# MCPS_Power_030524.net
KiCad netlist of a schematic drawn in Altium Designer
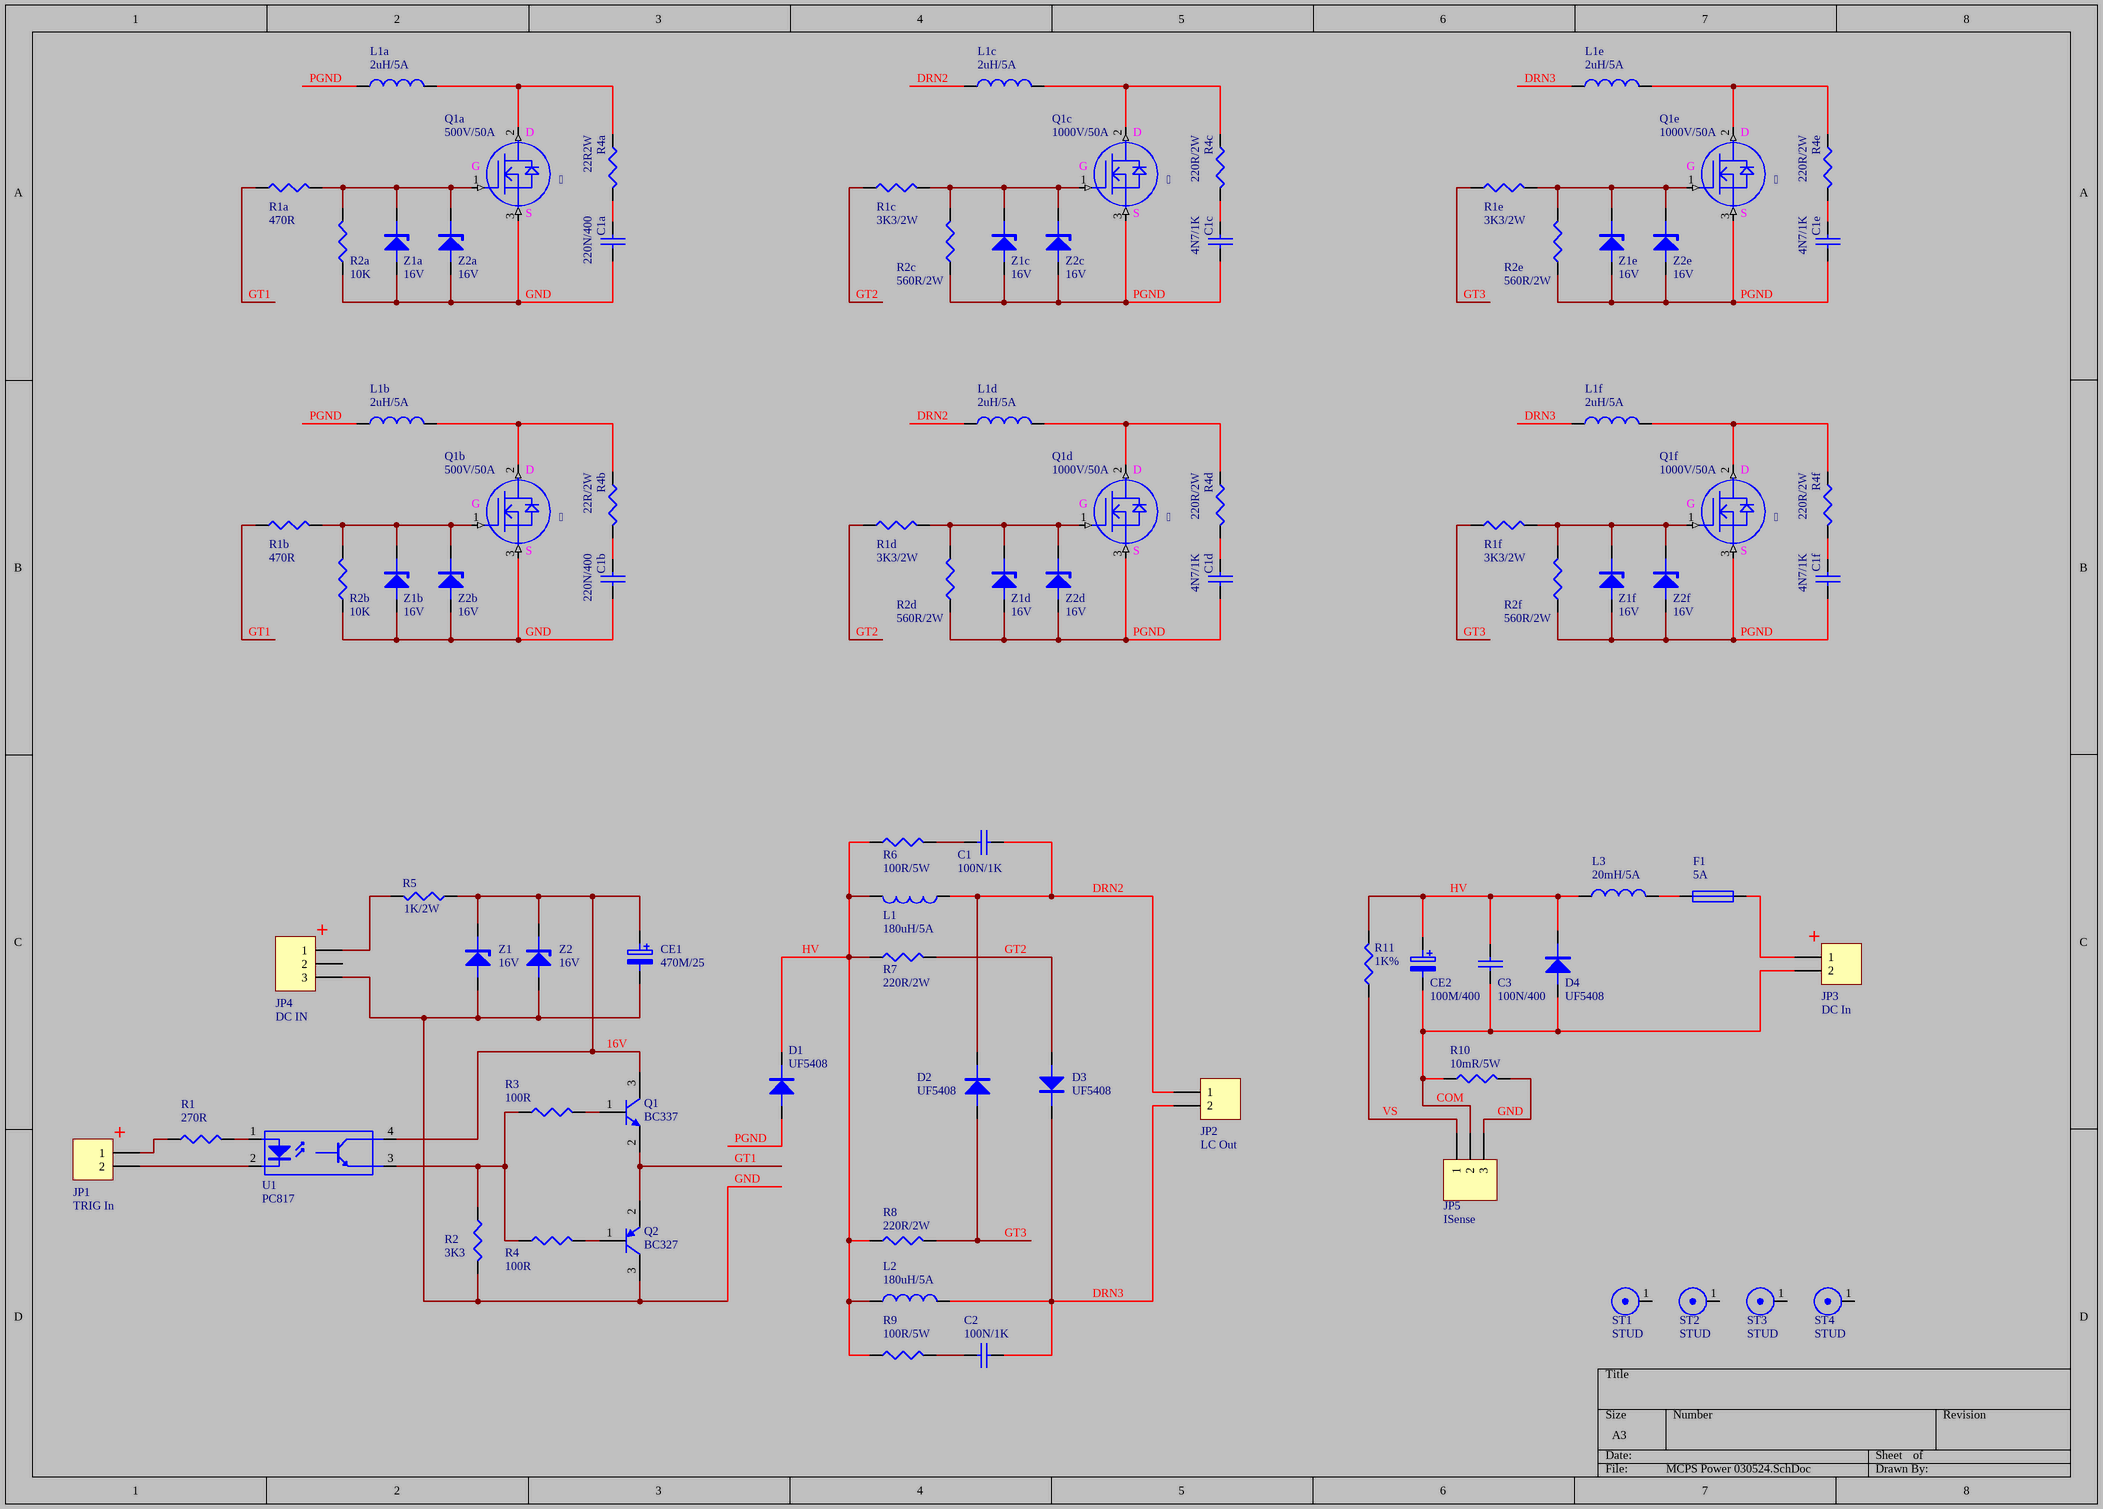
[diagram p0: MCPS Power 030524.SchDoc]

(export (version "E")
  (design (tool "Eeschema 10.0.6"))
  (components
    (comp (ref "C1") (value "100N/1K") (footprint "C100N") (libsource (lib "*") (part "C")))
    (comp (ref "C1a") (value "220N/400") (footprint "C4P") (libsource (lib "*") (part "C")))
    (comp (ref "C1b") (value "220N/400") (footprint "C4P") (libsource (lib "*") (part "C")))
    (comp (ref "C1c") (value "4N7/1K") (footprint "C4P") (libsource (lib "*") (part "C")))
    (comp (ref "C1d") (value "4N7/1K") (footprint "C4P") (libsource (lib "*") (part "C")))
    (comp (ref "C1e") (value "4N7/1K") (footprint "C4P") (libsource (lib "*") (part "C")))
    (comp (ref "C1f") (value "4N7/1K") (footprint "C4P") (libsource (lib "*") (part "C")))
    (comp (ref "C2") (value "100N/1K") (footprint "C100N") (libsource (lib "*") (part "C")))
    (comp (ref "C3") (value "100N/400") (footprint "C4P") (libsource (lib "*") (part "C")))
    (comp (ref "CE1") (value "470M/25") (footprint "cap2p12") (libsource (lib "*") (part "E")))
    (comp (ref "CE2") (value "100M/400") (footprint "CAP3P5") (libsource (lib "*") (part "E")))
    (comp (ref "D1") (value "UF5408") (footprint "D54") (libsource (lib "MyAltiumLib9702") (part "D")))
    (comp (ref "D2") (value "UF5408") (footprint "D54") (libsource (lib "MyAltiumLib9702") (part "D")))
    (comp (ref "D3") (value "UF5408") (footprint "D54") (libsource (lib "MyAltiumLib9702") (part "D")))
    (comp (ref "D4") (value "UF5408") (footprint "D54") (libsource (lib "MyAltiumLib9702") (part "D")))
    (comp (ref "F1") (value "5A") (footprint "FL") (libsource (lib "1402 Schlib 2020") (part "FUSE1")))
    (comp (ref "JP1")
      (value "TRIG In")
      (footprint "DSIP2")
      (description "Header, 2-Pin")
      (fields (field (name "PUBLISHER") "Altium Limited"))
      (libsource (lib "Miscellaneous Connectors") (part "Header 2"))
    )
    (comp (ref "JP2")
      (value "LC Out")
      (footprint "DG55X2")
      (description "Header, 2-Pin")
      (fields (field (name "PUBLISHER") "Altium Limited"))
      (libsource (lib "") (part "Header 2_1"))
    )
    (comp (ref "JP3")
      (value "DC In")
      (footprint "DG55X2")
      (description "Header, 2-Pin")
      (fields (field (name "PUBLISHER") "Altium Limited"))
      (libsource (lib "") (part "Header 2_1"))
    )
    (comp (ref "JP4")
      (value "DC IN")
      (footprint "DSIP3")
      (description "Header, 3-Pin")
      (fields (field (name "PUBLISHER") "Altium Limited"))
      (libsource (lib "") (part "Header 3_1"))
    )
    (comp (ref "JP5")
      (value "ISense")
      (footprint "DSIP3")
      (description "Header, 3-Pin")
      (fields (field (name "PUBLISHER") "Altium Limited"))
      (libsource (lib "1403 Schlib 2020") (part "Header 3"))
    )
    (comp (ref "L1") (value "180uH/5A") (footprint "L20MHGREEN") (libsource (lib "") (part "INDUCTOR_1")))
    (comp (ref "L1a")
      (value "2uH/5A")
      (footprint "LS_GREEN")
      (libsource (lib "MyAltiumLib9702") (part "INDUCTOR"))
    )
    (comp (ref "L1b")
      (value "2uH/5A")
      (footprint "LS_GREEN")
      (libsource (lib "MyAltiumLib9702") (part "INDUCTOR"))
    )
    (comp (ref "L1c")
      (value "2uH/5A")
      (footprint "LS_GREEN")
      (libsource (lib "MyAltiumLib9702") (part "INDUCTOR"))
    )
    (comp (ref "L1d")
      (value "2uH/5A")
      (footprint "LS_GREEN")
      (libsource (lib "MyAltiumLib9702") (part "INDUCTOR"))
    )
    (comp (ref "L1e")
      (value "2uH/5A")
      (footprint "LS_GREEN")
      (libsource (lib "MyAltiumLib9702") (part "INDUCTOR"))
    )
    (comp (ref "L1f")
      (value "2uH/5A")
      (footprint "LS_GREEN")
      (libsource (lib "MyAltiumLib9702") (part "INDUCTOR"))
    )
    (comp (ref "L2")
      (value "180uH/5A")
      (footprint "L20MHGREEN")
      (libsource (lib "MyAltiumLib9702") (part "INDUCTOR"))
    )
    (comp (ref "L3")
      (value "20mH/5A")
      (footprint "L20MHGREEN")
      (libsource (lib "MyAltiumLib9702") (part "INDUCTOR"))
    )
    (comp (ref "Q1")
      (value "BC337")
      (footprint "CBE-BC546")
      (libsource (lib "1402 Schlib 2020") (part "BC546"))
    )
    (comp (ref "Q1a")
      (value "")
      (footprint "3EDG-STR")
      (libsource (lib "1402 Schlib 2020") (part "MOSFET N"))
    )
    (comp (ref "Q1b")
      (value "")
      (footprint "3EDG-STR")
      (libsource (lib "1402 Schlib 2020") (part "MOSFET N"))
    )
    (comp (ref "Q1c")
      (value "")
      (footprint "3EDG-STR")
      (libsource (lib "1402 Schlib 2020") (part "MOSFET N"))
    )
    (comp (ref "Q1d")
      (value "")
      (footprint "3EDG-STR")
      (libsource (lib "1402 Schlib 2020") (part "MOSFET N"))
    )
    (comp (ref "Q1e")
      (value "")
      (footprint "3EDG-STR")
      (libsource (lib "1402 Schlib 2020") (part "MOSFET N"))
    )
    (comp (ref "Q1f")
      (value "")
      (footprint "3EDG-STR")
      (libsource (lib "1402 Schlib 2020") (part "MOSFET N"))
    )
    (comp (ref "Q2")
      (value "BC327")
      (footprint "CBE-BC546")
      (description "PNP")
      (fields (field (name "PUBLISHER") "Altium Limited"))
      (libsource (lib "1402 Schlib 2020") (part "M6"))
    )
    (comp (ref "R1") (value "270R") (footprint "W1/4") (libsource (lib "*") (part "R")))
    (comp (ref "R1a") (value "470R") (footprint "R5P") (libsource (lib "*") (part "R")))
    (comp (ref "R1b") (value "470R") (footprint "R5P") (libsource (lib "*") (part "R")))
    (comp (ref "R1c") (value "3K3/2W") (footprint "R2W") (libsource (lib "*") (part "R")))
    (comp (ref "R1d") (value "3K3/2W") (footprint "R2W") (libsource (lib "*") (part "R")))
    (comp (ref "R1e") (value "3K3/2W") (footprint "R2W") (libsource (lib "*") (part "R")))
    (comp (ref "R1f") (value "3K3/2W") (footprint "R2W") (libsource (lib "*") (part "R")))
    (comp (ref "R2") (value "3K3") (footprint "W1/4") (libsource (lib "*") (part "R")))
    (comp (ref "R2a") (value "10K") (footprint "R5P") (libsource (lib "*") (part "R")))
    (comp (ref "R2b") (value "10K") (footprint "R5P") (libsource (lib "*") (part "R")))
    (comp (ref "R2c") (value "560R/2W") (footprint "R2W") (libsource (lib "*") (part "R")))
    (comp (ref "R2d") (value "560R/2W") (footprint "R2W") (libsource (lib "*") (part "R")))
    (comp (ref "R2e") (value "560R/2W") (footprint "R2W") (libsource (lib "*") (part "R")))
    (comp (ref "R2f") (value "560R/2W") (footprint "R2W") (libsource (lib "*") (part "R")))
    (comp (ref "R3") (value "100R") (footprint "W1/4") (libsource (lib "*") (part "R")))
    (comp (ref "R4") (value "100R") (footprint "W1/4") (libsource (lib "*") (part "R")))
    (comp (ref "R4a") (value "22R2W") (footprint "R2W") (libsource (lib "*") (part "R")))
    (comp (ref "R4b") (value "22R/2W") (footprint "R2W") (libsource (lib "*") (part "R")))
    (comp (ref "R4c") (value "220R/2W") (footprint "R2W") (libsource (lib "*") (part "R")))
    (comp (ref "R4d") (value "220R/2W") (footprint "R2W") (libsource (lib "*") (part "R")))
    (comp (ref "R4e") (value "220R/2W") (footprint "R2W") (libsource (lib "*") (part "R")))
    (comp (ref "R4f") (value "220R/2W") (footprint "R2W") (libsource (lib "*") (part "R")))
    (comp (ref "R5") (value "1K/2W") (footprint "R2W") (libsource (lib "*") (part "R")))
    (comp (ref "R6") (value "100R/5W") (footprint "R5W") (libsource (lib "*") (part "R")))
    (comp (ref "R7") (value "220R/2W") (footprint "R2W") (libsource (lib "*") (part "R")))
    (comp (ref "R8") (value "220R/2W") (footprint "R2W") (libsource (lib "*") (part "R")))
    (comp (ref "R9") (value "100R/5W") (footprint "R5W") (libsource (lib "*") (part "R")))
    (comp (ref "R10") (value "10mR/5W") (footprint "R5W") (libsource (lib "*") (part "R")))
    (comp (ref "R11") (value "1K%") (footprint "R5P") (libsource (lib "*") (part "R")))
    (comp (ref "ST1") (value "STUD") (footprint "CORNER") (libsource (lib "1402 Schlib 2020") (part "STUD")))
    (comp (ref "ST2") (value "STUD") (footprint "CORNER") (libsource (lib "1402 Schlib 2020") (part "STUD")))
    (comp (ref "ST3") (value "STUD") (footprint "CORNER") (libsource (lib "1402 Schlib 2020") (part "STUD")))
    (comp (ref "ST4") (value "STUD") (footprint "CORNER") (libsource (lib "1402 Schlib 2020") (part "STUD")))
    (comp (ref "U1")
      (value "PC817")
      (footprint "DIP4")
      (libsource (lib "1402 Schlib 2020") (part "OPTODIP4"))
    )
    (comp (ref "Z1") (value "16V") (footprint "D5P") (libsource (lib "MyAltiumLib9702") (part "DZ")))
    (comp (ref "Z1a") (value "16V") (footprint "D5P") (libsource (lib "MyAltiumLib9702") (part "DZ")))
    (comp (ref "Z1b") (value "16V") (footprint "D5P") (libsource (lib "MyAltiumLib9702") (part "DZ")))
    (comp (ref "Z1c") (value "16V") (footprint "D5P") (libsource (lib "MyAltiumLib9702") (part "DZ")))
    (comp (ref "Z1d") (value "16V") (footprint "D5P") (libsource (lib "MyAltiumLib9702") (part "DZ")))
    (comp (ref "Z1e") (value "16V") (footprint "D5P") (libsource (lib "MyAltiumLib9702") (part "DZ")))
    (comp (ref "Z1f") (value "16V") (footprint "D5P") (libsource (lib "MyAltiumLib9702") (part "DZ")))
    (comp (ref "Z2") (value "16V") (footprint "D5P") (libsource (lib "MyAltiumLib9702") (part "DZ")))
    (comp (ref "Z2a") (value "16V") (footprint "D5P") (libsource (lib "MyAltiumLib9702") (part "DZ")))
    (comp (ref "Z2b") (value "16V") (footprint "D5P") (libsource (lib "MyAltiumLib9702") (part "DZ")))
    (comp (ref "Z2c") (value "16V") (footprint "D5P") (libsource (lib "MyAltiumLib9702") (part "DZ")))
    (comp (ref "Z2d") (value "16V") (footprint "D5P") (libsource (lib "MyAltiumLib9702") (part "DZ")))
    (comp (ref "Z2e") (value "16V") (footprint "D5P") (libsource (lib "MyAltiumLib9702") (part "DZ")))
    (comp (ref "Z2f") (value "16V") (footprint "D5P") (libsource (lib "MyAltiumLib9702") (part "DZ")))
  )
  (nets
    (net (code "1") (name "/16V") (class "Default")
      (node (ref "CE1") (pin "1") (pintype "passive"))
      (node (ref "Q1") (pin "3") (pinfunction "C_3") (pintype "passive"))
      (node (ref "R5") (pin "1") (pintype "passive"))
      (node (ref "U1") (pin "4") (pinfunction "C_4") (pintype "passive"))
      (node (ref "Z1") (pin "2") (pinfunction "K_2") (pintype "passive"))
      (node (ref "Z2") (pin "2") (pinfunction "K_2") (pintype "passive"))
    )
    (net (code "2") (name "/COM") (class "Default")
      (node (ref "C3") (pin "2") (pintype "passive"))
      (node (ref "CE2") (pin "2") (pintype "passive"))
      (node (ref "D4") (pin "1") (pinfunction "A_1") (pintype "passive"))
      (node (ref "JP3") (pin "2") (pinfunction "2_2") (pintype "passive"))
      (node (ref "JP5") (pin "2") (pinfunction "2_2") (pintype "passive"))
      (node (ref "R10") (pin "1") (pintype "passive"))
    )
    (net (code "3") (name "/DRN2") (class "Default")
      (node (ref "C1") (pin "2") (pintype "passive"))
      (node (ref "D2") (pin "2") (pinfunction "K_2") (pintype "passive"))
      (node (ref "JP2") (pin "1") (pinfunction "1_1") (pintype "passive"))
      (node (ref "L1") (pin "2") (pinfunction "2_2") (pintype "passive"))
      (node (ref "L1c") (pin "1") (pinfunction "1_1") (pintype "passive"))
      (node (ref "L1d") (pin "1") (pinfunction "1_1") (pintype "passive"))
    )
    (net (code "4") (name "/DRN3") (class "Default")
      (node (ref "C2") (pin "2") (pintype "passive"))
      (node (ref "D3") (pin "2") (pinfunction "K_2") (pintype "passive"))
      (node (ref "JP2") (pin "2") (pinfunction "2_2") (pintype "passive"))
      (node (ref "L1e") (pin "1") (pinfunction "1_1") (pintype "passive"))
      (node (ref "L1f") (pin "1") (pinfunction "1_1") (pintype "passive"))
      (node (ref "L2") (pin "2") (pinfunction "2_2") (pintype "passive"))
    )
    (net (code "5") (name "/GND") (class "Default")
      (node (ref "C1a") (pin "2") (pintype "passive"))
      (node (ref "C1b") (pin "2") (pintype "passive"))
      (node (ref "CE1") (pin "2") (pintype "passive"))
      (node (ref "JP4") (pin "3") (pinfunction "3_3") (pintype "passive"))
      (node (ref "JP5") (pin "3") (pinfunction "3_3") (pintype "passive"))
      (node (ref "Q1a") (pin "3") (pinfunction "S_3") (pintype "input"))
      (node (ref "Q1b") (pin "3") (pinfunction "S_3") (pintype "input"))
      (node (ref "Q2") (pin "3") (pinfunction "C_3") (pintype "passive"))
      (node (ref "R10") (pin "2") (pintype "passive"))
      (node (ref "R2") (pin "2") (pintype "passive"))
      (node (ref "R2a") (pin "1") (pintype "passive"))
      (node (ref "R2b") (pin "1") (pintype "passive"))
      (node (ref "Z1") (pin "1") (pinfunction "A_1") (pintype "passive"))
      (node (ref "Z1a") (pin "1") (pinfunction "A_1") (pintype "passive"))
      (node (ref "Z1b") (pin "1") (pinfunction "A_1") (pintype "passive"))
      (node (ref "Z2") (pin "1") (pinfunction "A_1") (pintype "passive"))
      (node (ref "Z2a") (pin "1") (pinfunction "A_1") (pintype "passive"))
      (node (ref "Z2b") (pin "1") (pinfunction "A_1") (pintype "passive"))
    )
    (net (code "6") (name "/GT1") (class "Default")
      (node (ref "Q1") (pin "2") (pinfunction "E_2") (pintype "passive"))
      (node (ref "Q2") (pin "2") (pinfunction "B_2") (pintype "passive"))
      (node (ref "R1a") (pin "1") (pintype "passive"))
      (node (ref "R1b") (pin "1") (pintype "passive"))
    )
    (net (code "7") (name "/GT2") (class "Default")
      (node (ref "D3") (pin "1") (pinfunction "A_1") (pintype "passive"))
      (node (ref "R1c") (pin "1") (pintype "passive"))
      (node (ref "R1d") (pin "1") (pintype "passive"))
      (node (ref "R7") (pin "2") (pintype "passive"))
    )
    (net (code "8") (name "/GT3") (class "Default")
      (node (ref "D2") (pin "1") (pinfunction "A_1") (pintype "passive"))
      (node (ref "R1e") (pin "1") (pintype "passive"))
      (node (ref "R1f") (pin "1") (pintype "passive"))
      (node (ref "R8") (pin "2") (pintype "passive"))
    )
    (net (code "9") (name "/HV") (class "Default")
      (node (ref "C3") (pin "1") (pintype "passive"))
      (node (ref "CE2") (pin "1") (pintype "passive"))
      (node (ref "D1") (pin "2") (pinfunction "K_2") (pintype "passive"))
      (node (ref "D4") (pin "2") (pinfunction "K_2") (pintype "passive"))
      (node (ref "L1") (pin "1") (pinfunction "1_1") (pintype "passive"))
      (node (ref "L2") (pin "1") (pinfunction "1_1") (pintype "passive"))
      (node (ref "L3") (pin "1") (pinfunction "1_1") (pintype "passive"))
      (node (ref "R11") (pin "2") (pintype "passive"))
      (node (ref "R6") (pin "1") (pintype "passive"))
      (node (ref "R7") (pin "1") (pintype "passive"))
      (node (ref "R8") (pin "1") (pintype "passive"))
      (node (ref "R9") (pin "1") (pintype "passive"))
    )
    (net (code "10") (name "/PGND") (class "Default")
      (node (ref "C1c") (pin "2") (pintype "passive"))
      (node (ref "C1d") (pin "2") (pintype "passive"))
      (node (ref "C1e") (pin "2") (pintype "passive"))
      (node (ref "C1f") (pin "2") (pintype "passive"))
      (node (ref "D1") (pin "1") (pinfunction "A_1") (pintype "passive"))
      (node (ref "L1a") (pin "1") (pinfunction "1_1") (pintype "passive"))
      (node (ref "L1b") (pin "1") (pinfunction "1_1") (pintype "passive"))
      (node (ref "Q1c") (pin "3") (pinfunction "S_3") (pintype "input"))
      (node (ref "Q1d") (pin "3") (pinfunction "S_3") (pintype "input"))
      (node (ref "Q1e") (pin "3") (pinfunction "S_3") (pintype "input"))
      (node (ref "Q1f") (pin "3") (pinfunction "S_3") (pintype "input"))
      (node (ref "R2c") (pin "1") (pintype "passive"))
      (node (ref "R2d") (pin "1") (pintype "passive"))
      (node (ref "R2e") (pin "1") (pintype "passive"))
      (node (ref "R2f") (pin "1") (pintype "passive"))
      (node (ref "Z1c") (pin "1") (pinfunction "A_1") (pintype "passive"))
      (node (ref "Z1d") (pin "1") (pinfunction "A_1") (pintype "passive"))
      (node (ref "Z1e") (pin "1") (pinfunction "A_1") (pintype "passive"))
      (node (ref "Z1f") (pin "1") (pinfunction "A_1") (pintype "passive"))
      (node (ref "Z2c") (pin "1") (pinfunction "A_1") (pintype "passive"))
      (node (ref "Z2d") (pin "1") (pinfunction "A_1") (pintype "passive"))
      (node (ref "Z2e") (pin "1") (pinfunction "A_1") (pintype "passive"))
      (node (ref "Z2f") (pin "1") (pinfunction "A_1") (pintype "passive"))
    )
    (net (code "11") (name "/VS") (class "Default")
      (node (ref "JP5") (pin "1") (pinfunction "1_1") (pintype "passive"))
      (node (ref "R11") (pin "1") (pintype "passive"))
    )
    (net (code "12") (name "Net-(C1-Pad1)") (class "Default")
      (node (ref "C1") (pin "1") (pintype "passive"))
      (node (ref "R6") (pin "2") (pintype "passive"))
    )
    (net (code "13") (name "Net-(C1a-Pad1)") (class "Default")
      (node (ref "C1a") (pin "1") (pintype "passive"))
      (node (ref "R4a") (pin "2") (pintype "passive"))
    )
    (net (code "14") (name "Net-(C1b-Pad1)") (class "Default")
      (node (ref "C1b") (pin "1") (pintype "passive"))
      (node (ref "R4b") (pin "2") (pintype "passive"))
    )
    (net (code "15") (name "Net-(C1c-Pad1)") (class "Default")
      (node (ref "C1c") (pin "1") (pintype "passive"))
      (node (ref "R4c") (pin "2") (pintype "passive"))
    )
    (net (code "16") (name "Net-(C1d-Pad1)") (class "Default")
      (node (ref "C1d") (pin "1") (pintype "passive"))
      (node (ref "R4d") (pin "2") (pintype "passive"))
    )
    (net (code "17") (name "Net-(C1e-Pad1)") (class "Default")
      (node (ref "C1e") (pin "1") (pintype "passive"))
      (node (ref "R4e") (pin "2") (pintype "passive"))
    )
    (net (code "18") (name "Net-(C1f-Pad1)") (class "Default")
      (node (ref "C1f") (pin "1") (pintype "passive"))
      (node (ref "R4f") (pin "2") (pintype "passive"))
    )
    (net (code "19") (name "Net-(C2-Pad1)") (class "Default")
      (node (ref "C2") (pin "1") (pintype "passive"))
      (node (ref "R9") (pin "2") (pintype "passive"))
    )
    (net (code "20") (name "Net-(F1-Pad1)") (class "Default")
      (node (ref "F1") (pin "1") (pintype "passive"))
      (node (ref "L3") (pin "2") (pinfunction "2_2") (pintype "passive"))
    )
    (net (code "21") (name "Net-(F1-Pad2)") (class "Default")
      (node (ref "F1") (pin "2") (pintype "passive"))
      (node (ref "JP3") (pin "1") (pinfunction "1_1") (pintype "passive"))
    )
    (net (code "22") (name "Net-(JP1-Pad1)") (class "Default")
      (node (ref "JP1") (pin "1") (pinfunction "1_1") (pintype "passive"))
      (node (ref "R1") (pin "1") (pintype "passive"))
    )
    (net (code "23") (name "Net-(JP4-Pad1)") (class "Default")
      (node (ref "JP4") (pin "1") (pinfunction "1_1") (pintype "passive"))
      (node (ref "R5") (pin "2") (pintype "passive"))
    )
    (net (code "24") (name "Net-(Q1-B)") (class "Default")
      (node (ref "Q1") (pin "1") (pinfunction "B_1") (pintype "passive"))
      (node (ref "R3") (pin "2") (pintype "passive"))
    )
    (net (code "25") (name "Net-(Q1a-D)") (class "Default")
      (node (ref "L1a") (pin "2") (pinfunction "2_2") (pintype "passive"))
      (node (ref "Q1a") (pin "2") (pinfunction "D_2") (pintype "output"))
      (node (ref "R4a") (pin "1") (pintype "passive"))
    )
    (net (code "26") (name "Net-(Q1a-G)") (class "Default")
      (node (ref "Q1a") (pin "1") (pinfunction "G_1") (pintype "input"))
      (node (ref "R1a") (pin "2") (pintype "passive"))
      (node (ref "R2a") (pin "2") (pintype "passive"))
      (node (ref "Z1a") (pin "2") (pinfunction "K_2") (pintype "passive"))
      (node (ref "Z2a") (pin "2") (pinfunction "K_2") (pintype "passive"))
    )
    (net (code "27") (name "Net-(Q1b-D)") (class "Default")
      (node (ref "L1b") (pin "2") (pinfunction "2_2") (pintype "passive"))
      (node (ref "Q1b") (pin "2") (pinfunction "D_2") (pintype "output"))
      (node (ref "R4b") (pin "1") (pintype "passive"))
    )
    (net (code "28") (name "Net-(Q1b-G)") (class "Default")
      (node (ref "Q1b") (pin "1") (pinfunction "G_1") (pintype "input"))
      (node (ref "R1b") (pin "2") (pintype "passive"))
      (node (ref "R2b") (pin "2") (pintype "passive"))
      (node (ref "Z1b") (pin "2") (pinfunction "K_2") (pintype "passive"))
      (node (ref "Z2b") (pin "2") (pinfunction "K_2") (pintype "passive"))
    )
    (net (code "29") (name "Net-(Q1c-D)") (class "Default")
      (node (ref "L1c") (pin "2") (pinfunction "2_2") (pintype "passive"))
      (node (ref "Q1c") (pin "2") (pinfunction "D_2") (pintype "output"))
      (node (ref "R4c") (pin "1") (pintype "passive"))
    )
    (net (code "30") (name "Net-(Q1c-G)") (class "Default")
      (node (ref "Q1c") (pin "1") (pinfunction "G_1") (pintype "input"))
      (node (ref "R1c") (pin "2") (pintype "passive"))
      (node (ref "R2c") (pin "2") (pintype "passive"))
      (node (ref "Z1c") (pin "2") (pinfunction "K_2") (pintype "passive"))
      (node (ref "Z2c") (pin "2") (pinfunction "K_2") (pintype "passive"))
    )
    (net (code "31") (name "Net-(Q1d-D)") (class "Default")
      (node (ref "L1d") (pin "2") (pinfunction "2_2") (pintype "passive"))
      (node (ref "Q1d") (pin "2") (pinfunction "D_2") (pintype "output"))
      (node (ref "R4d") (pin "1") (pintype "passive"))
    )
    (net (code "32") (name "Net-(Q1d-G)") (class "Default")
      (node (ref "Q1d") (pin "1") (pinfunction "G_1") (pintype "input"))
      (node (ref "R1d") (pin "2") (pintype "passive"))
      (node (ref "R2d") (pin "2") (pintype "passive"))
      (node (ref "Z1d") (pin "2") (pinfunction "K_2") (pintype "passive"))
      (node (ref "Z2d") (pin "2") (pinfunction "K_2") (pintype "passive"))
    )
    (net (code "33") (name "Net-(Q1e-D)") (class "Default")
      (node (ref "L1e") (pin "2") (pinfunction "2_2") (pintype "passive"))
      (node (ref "Q1e") (pin "2") (pinfunction "D_2") (pintype "output"))
      (node (ref "R4e") (pin "1") (pintype "passive"))
    )
    (net (code "34") (name "Net-(Q1e-G)") (class "Default")
      (node (ref "Q1e") (pin "1") (pinfunction "G_1") (pintype "input"))
      (node (ref "R1e") (pin "2") (pintype "passive"))
      (node (ref "R2e") (pin "2") (pintype "passive"))
      (node (ref "Z1e") (pin "2") (pinfunction "K_2") (pintype "passive"))
      (node (ref "Z2e") (pin "2") (pinfunction "K_2") (pintype "passive"))
    )
    (net (code "35") (name "Net-(Q1f-D)") (class "Default")
      (node (ref "L1f") (pin "2") (pinfunction "2_2") (pintype "passive"))
      (node (ref "Q1f") (pin "2") (pinfunction "D_2") (pintype "output"))
      (node (ref "R4f") (pin "1") (pintype "passive"))
    )
    (net (code "36") (name "Net-(Q1f-G)") (class "Default")
      (node (ref "Q1f") (pin "1") (pinfunction "G_1") (pintype "input"))
      (node (ref "R1f") (pin "2") (pintype "passive"))
      (node (ref "R2f") (pin "2") (pintype "passive"))
      (node (ref "Z1f") (pin "2") (pinfunction "K_2") (pintype "passive"))
      (node (ref "Z2f") (pin "2") (pinfunction "K_2") (pintype "passive"))
    )
    (net (code "37") (name "Net-(Q2-E)") (class "Default")
      (node (ref "Q2") (pin "1") (pinfunction "E_1") (pintype "passive"))
      (node (ref "R4") (pin "2") (pintype "passive"))
    )
    (net (code "38") (name "Net-(U1-A)") (class "Default")
      (node (ref "R1") (pin "2") (pintype "passive"))
      (node (ref "U1") (pin "1") (pinfunction "A_1") (pintype "passive"))
    )
    (net (code "39") (name "Net-(U1-E)") (class "Default")
      (node (ref "R2") (pin "1") (pintype "passive"))
      (node (ref "R3") (pin "1") (pintype "passive"))
      (node (ref "R4") (pin "1") (pintype "passive"))
      (node (ref "U1") (pin "3") (pinfunction "E_3") (pintype "passive"))
    )
    (net (code "40") (name "Net-(U1-K)") (class "Default")
      (node (ref "JP1") (pin "2") (pinfunction "2_2") (pintype "passive"))
      (node (ref "U1") (pin "2") (pinfunction "K_2") (pintype "passive"))
    )
    (net (code "41") (name "unconnected-(JP4-Pad2)") (class "Default")
      (node (ref "JP4") (pin "2") (pinfunction "2_2") (pintype "passive"))
    )
    (net (code "42") (name "unconnected-(ST1-Pad1)") (class "Default")
      (node (ref "ST1") (pin "1") (pintype "passive"))
    )
    (net (code "43") (name "unconnected-(ST2-Pad1)") (class "Default")
      (node (ref "ST2") (pin "1") (pintype "passive"))
    )
    (net (code "44") (name "unconnected-(ST3-Pad1)") (class "Default")
      (node (ref "ST3") (pin "1") (pintype "passive"))
    )
    (net (code "45") (name "unconnected-(ST4-Pad1)") (class "Default")
      (node (ref "ST4") (pin "1") (pintype "passive"))
    )
  )
)
